# stripped.net
KiCad netlist of a schematic drawn in Altium Designer
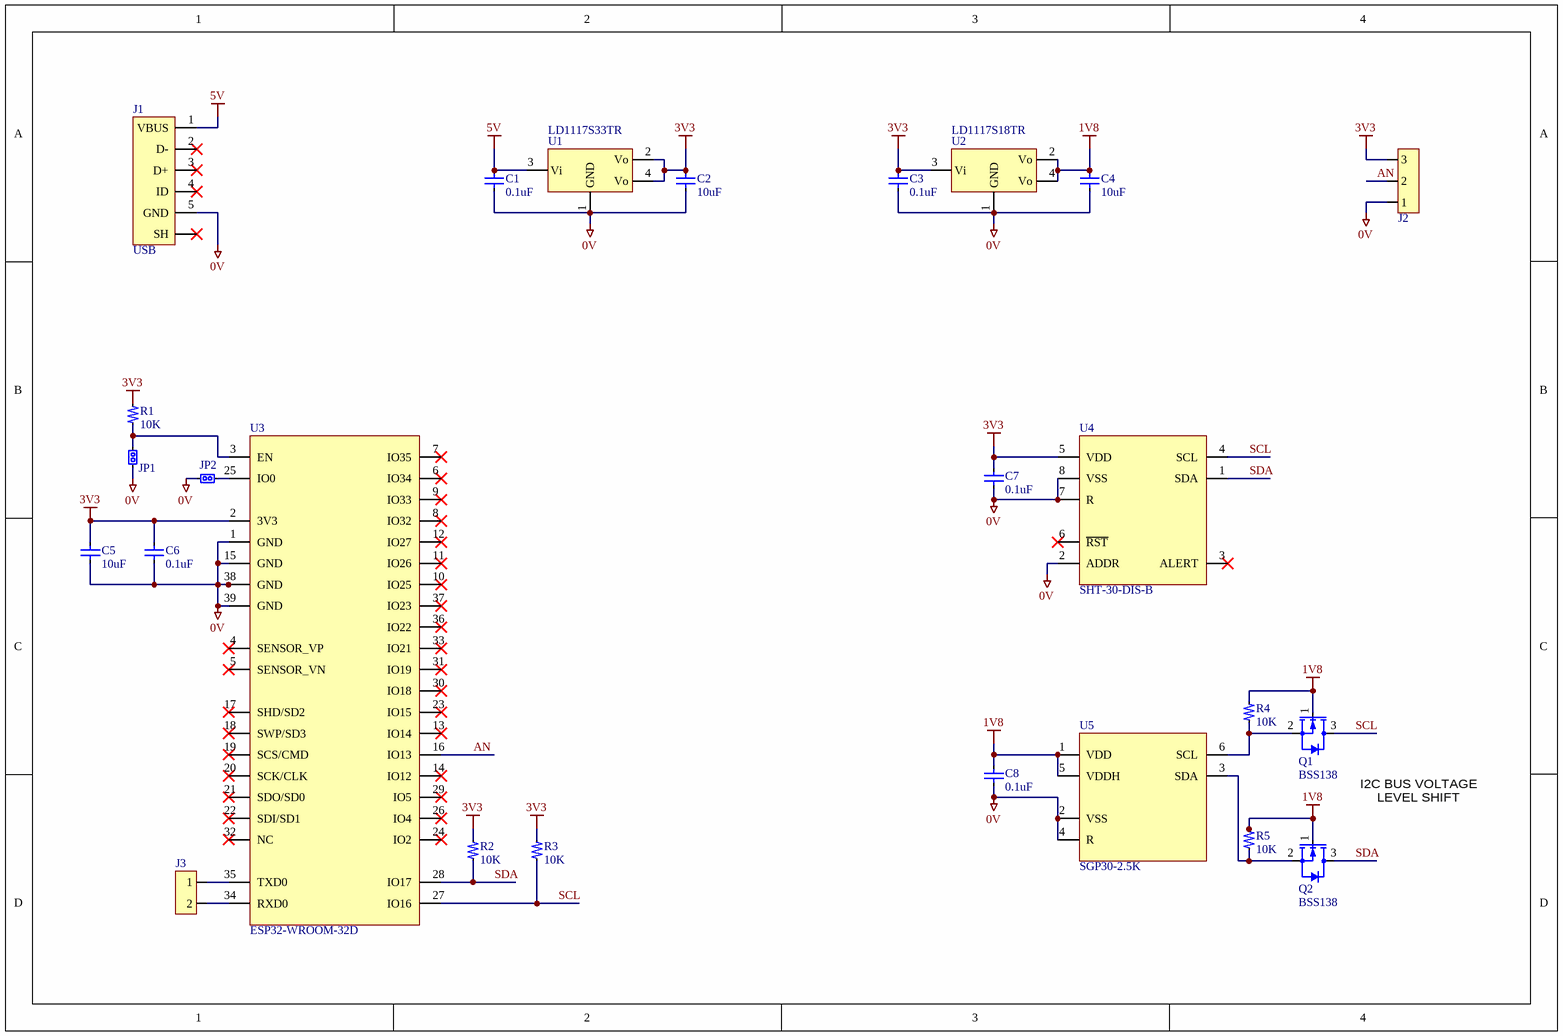
[diagram p0: stripped.SchDoc]

(export (version "E")
  (design (tool "Eeschema 10.0.6"))
  (components
    (comp (ref "C1")
      (value "0.1uF")
      (footprint "Capacitor_0603")
      (description "Generic capacitor symbol")
      (fields
        (field (name "MANUFACTURER") "Murata")
        (field (name "MANUFACTURER PART NUMBER") "GCM188R71C104KA37D")
      )
      (libsource (lib "Passives") (part "Capacitor"))
    )
    (comp (ref "C2")
      (value "10uF")
      (footprint "Capacitor_0603")
      (description "Generic capacitor symbol")
      (fields
        (field (name "MANUFACTURER") "Murata")
        (field (name "MANUFACTURER PART NUMBER") "GCM188R71C104KA37D")
      )
      (libsource (lib "Passives") (part "Capacitor"))
    )
    (comp (ref "C3")
      (value "0.1uF")
      (footprint "Capacitor_0603")
      (description "Generic capacitor symbol")
      (fields
        (field (name "MANUFACTURER") "Murata")
        (field (name "MANUFACTURER PART NUMBER") "GCM188R71C104KA37D")
      )
      (libsource (lib "Passives") (part "Capacitor"))
    )
    (comp (ref "C4")
      (value "10uF")
      (footprint "Capacitor_0603")
      (description "Generic capacitor symbol")
      (fields
        (field (name "MANUFACTURER") "Murata")
        (field (name "MANUFACTURER PART NUMBER") "GCM188R71C104KA37D")
      )
      (libsource (lib "Passives") (part "Capacitor"))
    )
    (comp (ref "C5")
      (value "10uF")
      (footprint "Capacitor_0603")
      (description "Generic capacitor symbol")
      (fields
        (field (name "MANUFACTURER") "Murata")
        (field (name "MANUFACTURER PART NUMBER") "GCM188R71C104KA37D")
      )
      (libsource (lib "Passives") (part "Capacitor"))
    )
    (comp (ref "C6")
      (value "0.1uF")
      (footprint "Capacitor_0603")
      (description "Generic capacitor symbol")
      (fields
        (field (name "MANUFACTURER") "Murata")
        (field (name "MANUFACTURER PART NUMBER") "GCM188R71C104KA37D")
      )
      (libsource (lib "Passives") (part "Capacitor"))
    )
    (comp (ref "C7")
      (value "0.1uF")
      (footprint "Capacitor_0603")
      (description "Generic capacitor symbol")
      (fields
        (field (name "MANUFACTURER") "Murata")
        (field (name "MANUFACTURER PART NUMBER") "GCM188R71C104KA37D")
      )
      (libsource (lib "Passives") (part "Capacitor"))
    )
    (comp (ref "C8")
      (value "0.1uF")
      (footprint "Capacitor_0603")
      (description "Generic capacitor symbol")
      (fields
        (field (name "MANUFACTURER") "Murata")
        (field (name "MANUFACTURER PART NUMBER") "GCM188R71C104KA37D")
      )
      (libsource (lib "Passives") (part "Capacitor"))
    )
    (comp (ref "J1")
      (value "USB")
      (footprint "CON_uUSB_NODRILL")
      (description "USB 2.0 Connector, Shielded, NoDrill")
      (libsource (lib "Connectors") (part "Con_USB_5pos+Shield_NoDrill"))
    )
    (comp (ref "J2")
      (value "3pin_TH_Via_Solder_Connector")
      (footprint "3pin_VIA_solder_connector")
      (description "NO-BOM")
      (libsource (lib "Utility") (part "3pin_TH_Via_Solder_Connector"))
    )
    (comp (ref "J3")
      (value "Con_2Pos_2.54mm_SMD")
      (footprint "1x2 SMD header")
      (description "2 position connector")
      (libsource (lib "Connectors") (part "Con_2Pos_2.54mm_SMD"))
    )
    (comp (ref "JP1")
      (value "0603")
      (footprint "pads_0603")
      (description "Jumper pads, 0603, no-BOM")
      (libsource (lib "Utility") (part "Jumper Pad 0603"))
    )
    (comp (ref "JP2")
      (value "0603")
      (footprint "pads_0603")
      (description "Jumper pads, 0603, no-BOM")
      (libsource (lib "Utility") (part "Jumper Pad 0603"))
    )
    (comp (ref "Q1")
      (value "BSS138")
      (footprint "SOT-23-3")
      (description "MOSFET N-CH 50V 220MA SOT-23")
      (libsource (lib "Discretes") (part "MFET_Nch"))
    )
    (comp (ref "Q2")
      (value "BSS138")
      (footprint "SOT-23-3")
      (description "MOSFET N-CH 50V 220MA SOT-23")
      (libsource (lib "Discretes") (part "MFET_Nch"))
    )
    (comp (ref "R1")
      (value "10K")
      (footprint "Resistor_0603")
      (description "Generic resistor symbol")
      (libsource (lib "Passives") (part "Resistor"))
    )
    (comp (ref "R2")
      (value "10K")
      (footprint "Resistor_0603")
      (description "Generic resistor symbol")
      (libsource (lib "Passives") (part "Resistor"))
    )
    (comp (ref "R3")
      (value "10K")
      (footprint "Resistor_0603")
      (description "Generic resistor symbol")
      (libsource (lib "Passives") (part "Resistor"))
    )
    (comp (ref "R4")
      (value "10K")
      (footprint "Resistor_0603")
      (description "Generic resistor symbol")
      (libsource (lib "Passives") (part "Resistor"))
    )
    (comp (ref "R5")
      (value "10K")
      (footprint "Resistor_0603")
      (description "Generic resistor symbol")
      (libsource (lib "Passives") (part "Resistor"))
    )
    (comp (ref "U1")
      (value "LD1117S33TR")
      (footprint "SOT-223")
      (description "Fixed 3V3 output LDO LD1117S33TR")
      (libsource (lib "Power") (part "LDO_3V3"))
    )
    (comp (ref "U2")
      (value "LD1117S18TR")
      (footprint "SOT-223")
      (description "Fixed 1V8 output LDO LD1117S18TR")
      (libsource (lib "Power") (part "LDO_1V8"))
    )
    (comp (ref "U3")
      (value "ESP32-WROOM-32D")
      (footprint "ESP_WROOM_32D")
      (description "ESP32 Module")
      (libsource (lib "ICs") (part "ESP32_WROOM"))
    )
    (comp (ref "U4")
      (value "SHT-30-DIS-B")
      (footprint "SHT3x_8-VFDFN_Exposed_Pad")
      (description "SENSOR HUMID/TEMP 5V I2C 3% SMD")
      (libsource (lib "ICs") (part "SHT-30"))
    )
    (comp (ref "U5")
      (value "SGP30-2.5K")
      (footprint "SGP30-2.5k")
      (description "SENSOR AIR QUALITY 2V I2C SMD")
      (libsource (lib "ICs") (part "SGP-30"))
    )
  )
  (nets
    (net (code "1") (name "/AN") (class "Default")
      (node (ref "J2") (pin "2") (pinfunction "2_2") (pintype "passive"))
      (node (ref "U3") (pin "16") (pinfunction "IO13_16") (pintype "passive"))
    )
    (net (code "2") (name "/SCL") (class "Default")
      (node (ref "Q1") (pin "3") (pinfunction "D_3") (pintype "passive"))
      (node (ref "R3") (pin "1") (pinfunction "1_1") (pintype "passive"))
      (node (ref "U3") (pin "27") (pinfunction "IO16_27") (pintype "passive"))
      (node (ref "U4") (pin "4") (pinfunction "SCL_4") (pintype "passive"))
    )
    (net (code "3") (name "/SDA") (class "Default")
      (node (ref "Q2") (pin "3") (pinfunction "D_3") (pintype "passive"))
      (node (ref "R2") (pin "1") (pinfunction "1_1") (pintype "passive"))
      (node (ref "U3") (pin "28") (pinfunction "IO17_28") (pintype "passive"))
      (node (ref "U4") (pin "1") (pinfunction "SDA_1") (pintype "passive"))
    )
    (net (code "4") (name "0V") (class "Default")
      (node (ref "C1") (pin "1") (pinfunction "1_1") (pintype "passive"))
      (node (ref "C2") (pin "2") (pinfunction "2_2") (pintype "passive"))
      (node (ref "C3") (pin "1") (pinfunction "1_1") (pintype "passive"))
      (node (ref "C4") (pin "1") (pinfunction "1_1") (pintype "passive"))
      (node (ref "C5") (pin "1") (pinfunction "1_1") (pintype "passive"))
      (node (ref "C6") (pin "1") (pinfunction "1_1") (pintype "passive"))
      (node (ref "C7") (pin "1") (pinfunction "1_1") (pintype "passive"))
      (node (ref "C8") (pin "1") (pinfunction "1_1") (pintype "passive"))
      (node (ref "J1") (pin "5") (pinfunction "GND_5") (pintype "passive"))
      (node (ref "J2") (pin "1") (pinfunction "1_1") (pintype "passive"))
      (node (ref "JP1") (pin "1") (pinfunction "1_1") (pintype "passive"))
      (node (ref "JP2") (pin "1") (pinfunction "1_1") (pintype "passive"))
      (node (ref "U1") (pin "1") (pinfunction "GND_1") (pintype "passive"))
      (node (ref "U2") (pin "1") (pinfunction "GND_1") (pintype "power_in"))
      (node (ref "U3") (pin "1") (pinfunction "GND_1") (pintype "passive"))
      (node (ref "U3") (pin "15") (pinfunction "GND_15") (pintype "passive"))
      (node (ref "U3") (pin "38") (pinfunction "GND_38") (pintype "passive"))
      (node (ref "U3") (pin "39") (pinfunction "GND_39") (pintype "passive"))
      (node (ref "U4") (pin "2") (pinfunction "ADDR_2") (pintype "passive"))
      (node (ref "U4") (pin "7") (pinfunction "R_7") (pintype "passive"))
      (node (ref "U4") (pin "8") (pinfunction "VSS_8") (pintype "passive"))
      (node (ref "U5") (pin "2") (pinfunction "VSS_2") (pintype "passive"))
      (node (ref "U5") (pin "4") (pinfunction "R_4") (pintype "passive"))
    )
    (net (code "5") (name "1V8") (class "Default")
      (node (ref "C4") (pin "2") (pinfunction "2_2") (pintype "passive"))
      (node (ref "C8") (pin "2") (pinfunction "2_2") (pintype "passive"))
      (node (ref "Q1") (pin "1") (pinfunction "G_1") (pintype "passive"))
      (node (ref "Q2") (pin "1") (pinfunction "G_1") (pintype "passive"))
      (node (ref "R4") (pin "2") (pinfunction "2_2") (pintype "passive"))
      (node (ref "R5") (pin "2") (pinfunction "2_2") (pintype "passive"))
      (node (ref "U2") (pin "2") (pinfunction "Vo_2") (pintype "power_in"))
      (node (ref "U2") (pin "4") (pinfunction "Vo_4") (pintype "power_in"))
      (node (ref "U5") (pin "1") (pinfunction "VDD_1") (pintype "passive"))
      (node (ref "U5") (pin "5") (pinfunction "VDDH_5") (pintype "passive"))
    )
    (net (code "6") (name "3V3") (class "Default")
      (node (ref "C2") (pin "1") (pinfunction "1_1") (pintype "passive"))
      (node (ref "C3") (pin "2") (pinfunction "2_2") (pintype "passive"))
      (node (ref "C5") (pin "2") (pinfunction "2_2") (pintype "passive"))
      (node (ref "C6") (pin "2") (pinfunction "2_2") (pintype "passive"))
      (node (ref "C7") (pin "2") (pinfunction "2_2") (pintype "passive"))
      (node (ref "J2") (pin "3") (pinfunction "3_3") (pintype "passive"))
      (node (ref "R1") (pin "2") (pinfunction "2_2") (pintype "passive"))
      (node (ref "R2") (pin "2") (pinfunction "2_2") (pintype "passive"))
      (node (ref "R3") (pin "2") (pinfunction "2_2") (pintype "passive"))
      (node (ref "U1") (pin "2") (pinfunction "Vo_2") (pintype "passive"))
      (node (ref "U1") (pin "4") (pinfunction "Vo_4") (pintype "passive"))
      (node (ref "U2") (pin "3") (pinfunction "Vi_3") (pintype "power_in"))
      (node (ref "U3") (pin "2") (pinfunction "3V3_2") (pintype "passive"))
      (node (ref "U4") (pin "5") (pinfunction "VDD_5") (pintype "passive"))
    )
    (net (code "7") (name "5V") (class "Default")
      (node (ref "C1") (pin "2") (pinfunction "2_2") (pintype "passive"))
      (node (ref "J1") (pin "1") (pinfunction "VBUS_1") (pintype "passive"))
      (node (ref "U1") (pin "3") (pinfunction "Vi_3") (pintype "passive"))
    )
    (net (code "8") (name "Net-(Q1-S)") (class "Default")
      (node (ref "Q1") (pin "2") (pinfunction "S_2") (pintype "passive"))
      (node (ref "R4") (pin "1") (pinfunction "1_1") (pintype "passive"))
      (node (ref "U5") (pin "6") (pinfunction "SCL_6") (pintype "passive"))
    )
    (net (code "9") (name "Net-(Q2-S)") (class "Default")
      (node (ref "Q2") (pin "2") (pinfunction "S_2") (pintype "passive"))
      (node (ref "R5") (pin "1") (pinfunction "1_1") (pintype "passive"))
      (node (ref "U5") (pin "3") (pinfunction "SDA_3") (pintype "passive"))
    )
    (net (code "10") (name "Net-(U3-EN)") (class "Default")
      (node (ref "JP1") (pin "2") (pinfunction "2_2") (pintype "passive"))
      (node (ref "R1") (pin "1") (pinfunction "1_1") (pintype "passive"))
      (node (ref "U3") (pin "3") (pinfunction "EN_3") (pintype "passive"))
    )
    (net (code "11") (name "Net-(U3-IO0)") (class "Default")
      (node (ref "JP2") (pin "2") (pinfunction "2_2") (pintype "passive"))
      (node (ref "U3") (pin "25") (pinfunction "IO0_25") (pintype "passive"))
    )
    (net (code "12") (name "Net-(U3-RXD0)") (class "Default")
      (node (ref "J3") (pin "2") (pinfunction "2_2") (pintype "passive"))
      (node (ref "U3") (pin "34") (pinfunction "RXD0_34") (pintype "passive"))
    )
    (net (code "13") (name "Net-(U3-TXD0)") (class "Default")
      (node (ref "J3") (pin "1") (pinfunction "1_1") (pintype "passive"))
      (node (ref "U3") (pin "35") (pinfunction "TXD0_35") (pintype "passive"))
    )
    (net (code "14") (name "unconnected-(J1-D+-Pad3)") (class "Default")
      (node (ref "J1") (pin "3") (pinfunction "D+_3") (pintype "passive+no_connect"))
    )
    (net (code "15") (name "unconnected-(J1-D--Pad2)") (class "Default")
      (node (ref "J1") (pin "2") (pinfunction "D-_2") (pintype "passive+no_connect"))
    )
    (net (code "16") (name "unconnected-(J1-ID-Pad4)") (class "Default")
      (node (ref "J1") (pin "4") (pinfunction "ID_4") (pintype "passive+no_connect"))
    )
    (net (code "17") (name "unconnected-(J1-PadSH)") (class "Default")
      (node (ref "J1") (pin "SH") (pinfunction "SH_SH") (pintype "passive+no_connect"))
    )
    (net (code "18") (name "unconnected-(U3-IO2-Pad24)") (class "Default")
      (node (ref "U3") (pin "24") (pinfunction "IO2_24") (pintype "passive+no_connect"))
    )
    (net (code "19") (name "unconnected-(U3-IO4-Pad26)") (class "Default")
      (node (ref "U3") (pin "26") (pinfunction "IO4_26") (pintype "passive+no_connect"))
    )
    (net (code "20") (name "unconnected-(U3-IO5-Pad29)") (class "Default")
      (node (ref "U3") (pin "29") (pinfunction "IO5_29") (pintype "passive+no_connect"))
    )
    (net (code "21") (name "unconnected-(U3-IO12-Pad14)") (class "Default")
      (node (ref "U3") (pin "14") (pinfunction "IO12_14") (pintype "passive+no_connect"))
    )
    (net (code "22") (name "unconnected-(U3-IO14-Pad13)") (class "Default")
      (node (ref "U3") (pin "13") (pinfunction "IO14_13") (pintype "passive+no_connect"))
    )
    (net (code "23") (name "unconnected-(U3-IO15-Pad23)") (class "Default")
      (node (ref "U3") (pin "23") (pinfunction "IO15_23") (pintype "passive+no_connect"))
    )
    (net (code "24") (name "unconnected-(U3-IO18-Pad30)") (class "Default")
      (node (ref "U3") (pin "30") (pinfunction "IO18_30") (pintype "passive+no_connect"))
    )
    (net (code "25") (name "unconnected-(U3-IO19-Pad31)") (class "Default")
      (node (ref "U3") (pin "31") (pinfunction "IO19_31") (pintype "passive+no_connect"))
    )
    (net (code "26") (name "unconnected-(U3-IO21-Pad33)") (class "Default")
      (node (ref "U3") (pin "33") (pinfunction "IO21_33") (pintype "passive+no_connect"))
    )
    (net (code "27") (name "unconnected-(U3-IO22-Pad36)") (class "Default")
      (node (ref "U3") (pin "36") (pinfunction "IO22_36") (pintype "passive+no_connect"))
    )
    (net (code "28") (name "unconnected-(U3-IO23-Pad37)") (class "Default")
      (node (ref "U3") (pin "37") (pinfunction "IO23_37") (pintype "passive+no_connect"))
    )
    (net (code "29") (name "unconnected-(U3-IO25-Pad10)") (class "Default")
      (node (ref "U3") (pin "10") (pinfunction "IO25_10") (pintype "passive+no_connect"))
    )
    (net (code "30") (name "unconnected-(U3-IO26-Pad11)") (class "Default")
      (node (ref "U3") (pin "11") (pinfunction "IO26_11") (pintype "passive+no_connect"))
    )
    (net (code "31") (name "unconnected-(U3-IO27-Pad12)") (class "Default")
      (node (ref "U3") (pin "12") (pinfunction "IO27_12") (pintype "passive+no_connect"))
    )
    (net (code "32") (name "unconnected-(U3-IO32-Pad8)") (class "Default")
      (node (ref "U3") (pin "8") (pinfunction "IO32_8") (pintype "passive+no_connect"))
    )
    (net (code "33") (name "unconnected-(U3-IO33-Pad9)") (class "Default")
      (node (ref "U3") (pin "9") (pinfunction "IO33_9") (pintype "passive+no_connect"))
    )
    (net (code "34") (name "unconnected-(U3-IO34-Pad6)") (class "Default")
      (node (ref "U3") (pin "6") (pinfunction "IO34_6") (pintype "passive+no_connect"))
    )
    (net (code "35") (name "unconnected-(U3-IO35-Pad7)") (class "Default")
      (node (ref "U3") (pin "7") (pinfunction "IO35_7") (pintype "passive+no_connect"))
    )
    (net (code "36") (name "unconnected-(U3-NC-Pad32)") (class "Default")
      (node (ref "U3") (pin "32") (pinfunction "NC_32") (pintype "passive+no_connect"))
    )
    (net (code "37") (name "unconnected-(U3-SCK{slash}CLK-Pad20)") (class "Default")
      (node (ref "U3") (pin "20") (pinfunction "SCK/CLK_20") (pintype "passive+no_connect"))
    )
    (net (code "38") (name "unconnected-(U3-SCS{slash}CMD-Pad19)") (class "Default")
      (node (ref "U3") (pin "19") (pinfunction "SCS/CMD_19") (pintype "passive+no_connect"))
    )
    (net (code "39") (name "unconnected-(U3-SDI{slash}SD1-Pad22)") (class "Default")
      (node (ref "U3") (pin "22") (pinfunction "SDI/SD1_22") (pintype "passive+no_connect"))
    )
    (net (code "40") (name "unconnected-(U3-SDO{slash}SD0-Pad21)") (class "Default")
      (node (ref "U3") (pin "21") (pinfunction "SDO/SD0_21") (pintype "passive+no_connect"))
    )
    (net (code "41") (name "unconnected-(U3-SENSOR_VN-Pad5)") (class "Default")
      (node (ref "U3") (pin "5") (pinfunction "SENSOR_VN_5") (pintype "passive+no_connect"))
    )
    (net (code "42") (name "unconnected-(U3-SENSOR_VP-Pad4)") (class "Default")
      (node (ref "U3") (pin "4") (pinfunction "SENSOR_VP_4") (pintype "passive+no_connect"))
    )
    (net (code "43") (name "unconnected-(U3-SHD{slash}SD2-Pad17)") (class "Default")
      (node (ref "U3") (pin "17") (pinfunction "SHD/SD2_17") (pintype "passive+no_connect"))
    )
    (net (code "44") (name "unconnected-(U3-SWP{slash}SD3-Pad18)") (class "Default")
      (node (ref "U3") (pin "18") (pinfunction "SWP/SD3_18") (pintype "passive+no_connect"))
    )
    (net (code "45") (name "unconnected-(U4-ALERT-Pad3)") (class "Default")
      (node (ref "U4") (pin "3") (pinfunction "ALERT_3") (pintype "passive+no_connect"))
    )
    (net (code "46") (name "unconnected-(U4-~{RST}-Pad6)") (class "Default")
      (node (ref "U4") (pin "6") (pinfunction "~{RST}_6") (pintype "passive+no_connect"))
    )
  )
)
